# BAT.net
KiCad netlist of a schematic drawn in Altium Designer
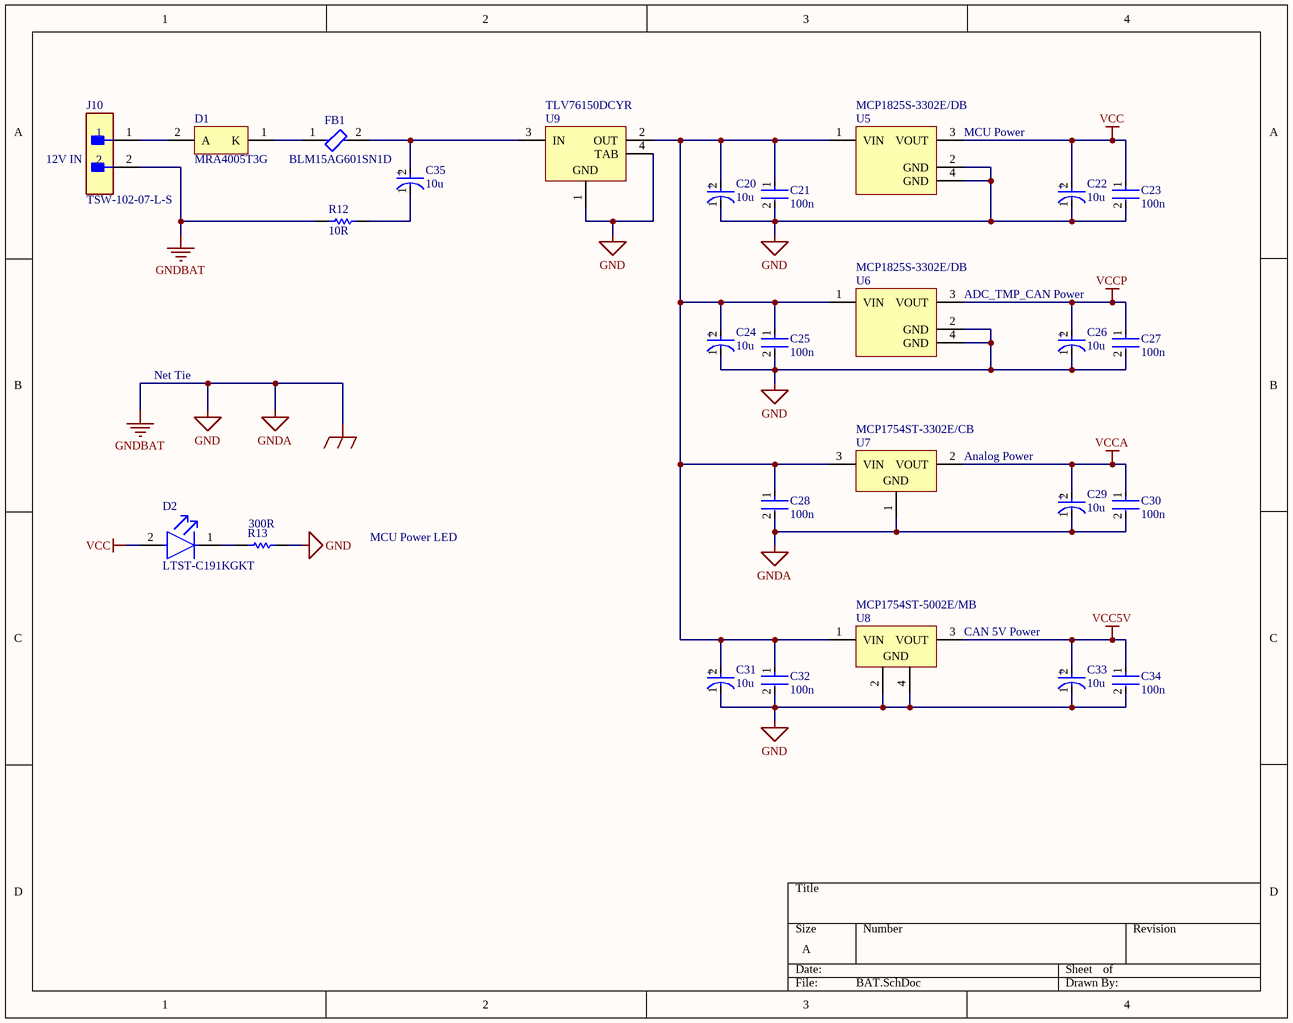
[diagram p0: BAT.SchDoc]

(export (version "E")
  (design (tool "Eeschema 10.0.6"))
  (components
    (comp (ref "C20")
      (value "10u")
      (footprint "FP-TAJA-MFG")
      (description "10uF 6.3V  ±10% 4Ω 1206  SMD Tantalum Capacitor")
      (fields (field (name "VOLTAGE") "6.3V") (field (name "TOLERANCE") "20%"))
      (libsource (lib "Altium Content Vault") (part "203bc49f2ac43e59fd269a8c329ed05"))
    )
    (comp (ref "C21")
      (value "100n")
      (footprint "FP-GRM033-0_03-MFG")
      (description "Chip Multilayer Ceramic Capacitors for General Purpose, 0201, 0.10uF, X5R, 15%, 10%, 6.3V")
      (fields (field (name "VOLTAGE") "6.3V") (field (name "TOLERANCE") "10%"))
      (libsource (lib "Altium Content Vault") (part "b4654b650e69147ec39a6b967a45e02"))
    )
    (comp (ref "C22")
      (value "10u")
      (footprint "FP-TAJA-MFG")
      (description "10uF 6.3V  ±10% 4Ω 1206  SMD Tantalum Capacitor")
      (fields (field (name "VOLTAGE") "6.3V") (field (name "TOLERANCE") "20%"))
      (libsource (lib "Altium Content Vault") (part "203bc49f2ac43e59fd269a8c329ed05"))
    )
    (comp (ref "C23")
      (value "100n")
      (footprint "FP-GRM033-0_03-MFG")
      (description "Chip Multilayer Ceramic Capacitors for General Purpose, 0201, 0.10uF, X5R, 15%, 10%, 6.3V")
      (fields (field (name "VOLTAGE") "6.3V") (field (name "TOLERANCE") "10%"))
      (libsource (lib "Altium Content Vault") (part "b4654b650e69147ec39a6b967a45e02"))
    )
    (comp (ref "C24")
      (value "10u")
      (footprint "FP-TAJA-MFG")
      (description "10uF 6.3V  ±10% 4Ω 1206  SMD Tantalum Capacitor")
      (fields (field (name "VOLTAGE") "6.3V") (field (name "TOLERANCE") "20%"))
      (libsource (lib "Altium Content Vault") (part "203bc49f2ac43e59fd269a8c329ed05"))
    )
    (comp (ref "C25")
      (value "100n")
      (footprint "FP-GRM033-0_03-MFG")
      (description "Chip Multilayer Ceramic Capacitors for General Purpose, 0201, 0.10uF, X5R, 15%, 10%, 6.3V")
      (fields (field (name "VOLTAGE") "6.3V") (field (name "TOLERANCE") "10%"))
      (libsource (lib "Altium Content Vault") (part "b4654b650e69147ec39a6b967a45e02"))
    )
    (comp (ref "C26")
      (value "10u")
      (footprint "FP-TAJA-MFG")
      (description "10uF 6.3V  ±10% 4Ω 1206  SMD Tantalum Capacitor")
      (fields (field (name "VOLTAGE") "6.3V") (field (name "TOLERANCE") "20%"))
      (libsource (lib "Altium Content Vault") (part "203bc49f2ac43e59fd269a8c329ed05"))
    )
    (comp (ref "C27")
      (value "100n")
      (footprint "FP-GRM033-0_03-MFG")
      (description "Chip Multilayer Ceramic Capacitors for General Purpose, 0201, 0.10uF, X5R, 15%, 10%, 6.3V")
      (fields (field (name "VOLTAGE") "6.3V") (field (name "TOLERANCE") "10%"))
      (libsource (lib "Altium Content Vault") (part "b4654b650e69147ec39a6b967a45e02"))
    )
    (comp (ref "C28")
      (value "100n")
      (footprint "FP-GRM033-0_03-MFG")
      (description "Chip Multilayer Ceramic Capacitors for General Purpose, 0201, 0.10uF, X5R, 15%, 10%, 6.3V")
      (fields (field (name "VOLTAGE") "6.3V") (field (name "TOLERANCE") "10%"))
      (libsource (lib "Altium Content Vault") (part "b4654b650e69147ec39a6b967a45e02"))
    )
    (comp (ref "C29")
      (value "10u")
      (footprint "FP-TAJA-MFG")
      (description "10uF 6.3V  ±10% 4Ω 1206  SMD Tantalum Capacitor")
      (fields (field (name "VOLTAGE") "6.3V") (field (name "TOLERANCE") "20%"))
      (libsource (lib "Altium Content Vault") (part "203bc49f2ac43e59fd269a8c329ed05"))
    )
    (comp (ref "C30")
      (value "100n")
      (footprint "FP-GRM033-0_03-MFG")
      (description "Chip Multilayer Ceramic Capacitors for General Purpose, 0201, 0.10uF, X5R, 15%, 10%, 6.3V")
      (fields (field (name "VOLTAGE") "6.3V") (field (name "TOLERANCE") "10%"))
      (libsource (lib "Altium Content Vault") (part "b4654b650e69147ec39a6b967a45e02"))
    )
    (comp (ref "C31")
      (value "10u")
      (footprint "FP-TAJA-MFG")
      (description "10uF 6.3V  ±10% 4Ω 1206  SMD Tantalum Capacitor")
      (fields (field (name "VOLTAGE") "6.3V") (field (name "TOLERANCE") "20%"))
      (libsource (lib "Altium Content Vault") (part "203bc49f2ac43e59fd269a8c329ed05"))
    )
    (comp (ref "C32")
      (value "100n")
      (footprint "FP-GRM033-0_03-MFG")
      (description "Chip Multilayer Ceramic Capacitors for General Purpose, 0201, 0.10uF, X5R, 15%, 10%, 6.3V")
      (fields (field (name "VOLTAGE") "6.3V") (field (name "TOLERANCE") "10%"))
      (libsource (lib "Altium Content Vault") (part "b4654b650e69147ec39a6b967a45e02"))
    )
    (comp (ref "C33")
      (value "10u")
      (footprint "FP-TAJA-MFG")
      (description "10uF 6.3V  ±10% 4Ω 1206  SMD Tantalum Capacitor")
      (fields (field (name "VOLTAGE") "6.3V") (field (name "TOLERANCE") "20%"))
      (libsource (lib "Altium Content Vault") (part "203bc49f2ac43e59fd269a8c329ed05"))
    )
    (comp (ref "C34")
      (value "100n")
      (footprint "FP-GRM033-0_03-MFG")
      (description "Chip Multilayer Ceramic Capacitors for General Purpose, 0201, 0.10uF, X5R, 15%, 10%, 6.3V")
      (fields (field (name "VOLTAGE") "6.3V") (field (name "TOLERANCE") "10%"))
      (libsource (lib "Altium Content Vault") (part "b4654b650e69147ec39a6b967a45e02"))
    )
    (comp (ref "C35")
      (value "10u")
      (footprint "FP-TAJA-MFG")
      (description "10uF 6.3V  ±10% 4Ω 1206  SMD Tantalum Capacitor")
      (fields (field (name "VOLTAGE") "6.3V") (field (name "TOLERANCE") "20%"))
      (libsource (lib "Altium Content Vault") (part "203bc49f2ac43e59fd269a8c329ed05"))
    )
    (comp (ref "D1")
      (value "MRA4005T3G")
      (footprint "ONSC-SMA-2-403D-02_V")
      (description "Surface Mount Standard Recovery Power Rectifier, 2-Pin SMA, Pb-Free, Tape and Reel")
      (fields (field (name "MANUFACTURER") "On Semiconductor"))
      (libsource (lib "Altium Content Vault") (part "ONSC-D-K1A2-2_A"))
    )
    (comp (ref "D2")
      (value "LTST-C191KGKT")
      (footprint "FP-LTST-C191KSKT-MFG")
      (description "LED YELLOW CLEAR SMD")
      (libsource (lib "Altium Content Vault") (part "8706943c75ba83719d021d2fdc84c58"))
    )
    (comp (ref "FB1")
      (value "BLM15AG601SN1D")
      (footprint "FP-BLM15-0_05-MFG")
      (description "Chip Ferrite Bead, 0402, 600Ω @ 100MHz, 0.52Ω, 25%, 300mA")
      (fields (field (name "TOLERANCE") "25%"))
      (libsource (lib "Altium Content Vault") (part "5f30dd21d616792df468990f7003faa"))
    )
    (comp (ref "J10")
      (value "TSW-102-07-L-S")
      (footprint "FP-TSW-102-07-L-S-MFG")
      (description "CONN HEADER VERT 2POS 2.54MM")
      (libsource (lib "Altium Content Vault") (part "3bc925449376181038e59eaffc5286c"))
    )
    (comp (ref "R12")
      (value "10R")
      (footprint "RESC2013X60X35ML10T20")
      (description "Chip Resistor, 10 Ohm, +/- 1%, 0.125 W, -55 to 155 degC, 0805 (2012 Metric), RoHS, Tape and Reel")
      (fields (field (name "MANUFACTURER") "Yageo") (field (name "TOLERANCE") "1%"))
      (libsource (lib "Altium Content Vault") (part "RES-2"))
    )
    (comp (ref "R13")
      (value "300R")
      (footprint "RESC1608X55X30LL20T20")
      (fields (field (name "PART NUMBER") "ERA3AEB301V") (field (name "MANUFACTURER") "Panasonic"))
      (libsource (lib "Altium Content Vault") (part "RES"))
    )
    (comp (ref "U5")
      (value "MCP1825S-3302E/DB")
      (footprint "SOT-223-DB3_N")
      (description "500 mA, Low Voltage, Low Quiescent Current LDO Regulator, 3-Pin SOT-223, Extended Temperature")
      (libsource (lib "Altium Content Vault") (part "PM-LINEREG-MCP1825-IL4"))
    )
    (comp (ref "U6")
      (value "MCP1825S-3302E/DB")
      (footprint "SOT-223-DB3_N")
      (description "500 mA, Low Voltage, Low Quiescent Current LDO Regulator, 3-Pin SOT-223, Extended Temperature")
      (libsource (lib "Altium Content Vault") (part "PM-LINEREG-MCP1825-IL4"))
    )
    (comp (ref "U7")
      (value "MCP1754ST-3302E/CB")
      (footprint "MCHP-SOT-23A-CB3_N")
      (description "150 mA, 16 V, High Performance LDO, -40 to 125 degC, 3-pin SOT-23A (CB3), Tape and Reel")
      (fields (field (name "MANUFACTURER") "Microchip"))
      (libsource (lib "Altium Content Vault") (part "MCHP-MCP17XX-SOT-23X-3"))
    )
    (comp (ref "U8")
      (value "MCP1754ST-5002E/MB")
      (footprint "MCHP-SOT-89-MB3_L")
      (description "150 mA, 16 V, High Performance LDO, -40 to 125 degC, 3-pin SOT-89 (MB3), Tape and Reel")
      (fields (field (name "MANUFACTURER") "Microchip"))
      (libsource (lib "Altium Content Vault") (part "MCHP-MCP1754S-SOT-xxx"))
    )
    (comp (ref "U9")
      (value "TLV76150DCYR")
      (footprint "DCY0004A_L")
      (description "800mA Low-Dropout Linear Regulator, 4-pin SOT-223")
      (fields (field (name "PARTNUMBER") "LM1117MPX-5.0") (field (name "MANUFACTURER") "Texas Instruments"))
      (libsource (lib "Altium Content Vault") (part "PM-REG-LM1086-SOT4"))
    )
  )
  (nets
    (net (code "1") (name "GND") (class "Default")
      (node (ref "C20") (pin "1") (pinfunction "C_1") (pintype "passive"))
      (node (ref "C21") (pin "2") (pinfunction "2_2") (pintype "passive"))
      (node (ref "C22") (pin "1") (pinfunction "C_1") (pintype "passive"))
      (node (ref "C23") (pin "2") (pinfunction "2_2") (pintype "passive"))
      (node (ref "C24") (pin "1") (pinfunction "C_1") (pintype "passive"))
      (node (ref "C25") (pin "2") (pinfunction "2_2") (pintype "passive"))
      (node (ref "C26") (pin "1") (pinfunction "C_1") (pintype "passive"))
      (node (ref "C27") (pin "2") (pinfunction "2_2") (pintype "passive"))
      (node (ref "C28") (pin "2") (pinfunction "2_2") (pintype "passive"))
      (node (ref "C29") (pin "1") (pinfunction "C_1") (pintype "passive"))
      (node (ref "C30") (pin "2") (pinfunction "2_2") (pintype "passive"))
      (node (ref "C31") (pin "1") (pinfunction "C_1") (pintype "passive"))
      (node (ref "C32") (pin "2") (pinfunction "2_2") (pintype "passive"))
      (node (ref "C33") (pin "1") (pinfunction "C_1") (pintype "passive"))
      (node (ref "C34") (pin "2") (pinfunction "2_2") (pintype "passive"))
      (node (ref "J10") (pin "2") (pinfunction "2_2") (pintype "passive"))
      (node (ref "R12") (pin "1") (pinfunction "1_1") (pintype "passive"))
      (node (ref "R13") (pin "2") (pinfunction "2_2") (pintype "passive"))
      (node (ref "U5") (pin "2") (pinfunction "GND_2") (pintype "power_in"))
      (node (ref "U5") (pin "4") (pinfunction "GND_4") (pintype "power_in"))
      (node (ref "U6") (pin "2") (pinfunction "GND_2") (pintype "power_in"))
      (node (ref "U6") (pin "4") (pinfunction "GND_4") (pintype "power_in"))
      (node (ref "U7") (pin "1") (pinfunction "GND_1") (pintype "power_in"))
      (node (ref "U8") (pin "2") (pinfunction "GND_2") (pintype "power_in"))
      (node (ref "U8") (pin "4") (pinfunction "GND_4") (pintype "power_in"))
      (node (ref "U9") (pin "1") (pinfunction "GND_1") (pintype "power_in"))
      (node (ref "U9") (pin "4") (pinfunction "TAB_4") (pintype "power_in"))
    )
    (net (code "2") (name "Net-(C20-A)") (class "Default")
      (node (ref "C20") (pin "2") (pinfunction "A_2") (pintype "passive"))
      (node (ref "C21") (pin "1") (pinfunction "1_1") (pintype "passive"))
      (node (ref "C24") (pin "2") (pinfunction "A_2") (pintype "passive"))
      (node (ref "C25") (pin "1") (pinfunction "1_1") (pintype "passive"))
      (node (ref "C28") (pin "1") (pinfunction "1_1") (pintype "passive"))
      (node (ref "C31") (pin "2") (pinfunction "A_2") (pintype "passive"))
      (node (ref "C32") (pin "1") (pinfunction "1_1") (pintype "passive"))
      (node (ref "U5") (pin "1") (pinfunction "VIN_1") (pintype "power_in"))
      (node (ref "U6") (pin "1") (pinfunction "VIN_1") (pintype "power_in"))
      (node (ref "U7") (pin "3") (pinfunction "VIN_3") (pintype "power_in"))
      (node (ref "U8") (pin "1") (pinfunction "VIN_1") (pintype "power_in"))
      (node (ref "U9") (pin "2") (pinfunction "OUT_2") (pintype "power_in"))
    )
    (net (code "3") (name "Net-(C35-A)") (class "Default")
      (node (ref "C35") (pin "2") (pinfunction "A_2") (pintype "passive"))
      (node (ref "FB1") (pin "2") (pinfunction "2_2") (pintype "passive"))
      (node (ref "U9") (pin "3") (pinfunction "IN_3") (pintype "power_in"))
    )
    (net (code "4") (name "Net-(C35-C)") (class "Default")
      (node (ref "C35") (pin "1") (pinfunction "C_1") (pintype "passive"))
      (node (ref "R12") (pin "2") (pinfunction "2_2") (pintype "passive"))
    )
    (net (code "5") (name "Net-(D1-A)") (class "Default")
      (node (ref "D1") (pin "2") (pinfunction "A_2") (pintype "passive"))
      (node (ref "J10") (pin "1") (pinfunction "1_1") (pintype "passive"))
    )
    (net (code "6") (name "Net-(D1-K)") (class "Default")
      (node (ref "D1") (pin "1") (pinfunction "K_1") (pintype "passive"))
      (node (ref "FB1") (pin "1") (pinfunction "1_1") (pintype "passive"))
    )
    (net (code "7") (name "Net-(D2-C)") (class "Default")
      (node (ref "D2") (pin "1") (pinfunction "C_1") (pintype "passive"))
      (node (ref "R13") (pin "1") (pinfunction "1_1") (pintype "passive"))
    )
    (net (code "8") (name "VCC") (class "Default")
      (node (ref "C22") (pin "2") (pinfunction "A_2") (pintype "passive"))
      (node (ref "C23") (pin "1") (pinfunction "1_1") (pintype "passive"))
      (node (ref "D2") (pin "2") (pinfunction "A_2") (pintype "passive"))
      (node (ref "U5") (pin "3") (pinfunction "VOUT_3") (pintype "power_in"))
    )
    (net (code "9") (name "VCC5V") (class "Default")
      (node (ref "C33") (pin "2") (pinfunction "A_2") (pintype "passive"))
      (node (ref "C34") (pin "1") (pinfunction "1_1") (pintype "passive"))
      (node (ref "U8") (pin "3") (pinfunction "VOUT_3") (pintype "power_in"))
    )
    (net (code "10") (name "VCCA") (class "Default")
      (node (ref "C29") (pin "2") (pinfunction "A_2") (pintype "passive"))
      (node (ref "C30") (pin "1") (pinfunction "1_1") (pintype "passive"))
      (node (ref "U7") (pin "2") (pinfunction "VOUT_2") (pintype "power_in"))
    )
    (net (code "11") (name "VCCP") (class "Default")
      (node (ref "C26") (pin "2") (pinfunction "A_2") (pintype "passive"))
      (node (ref "C27") (pin "1") (pinfunction "1_1") (pintype "passive"))
      (node (ref "U6") (pin "3") (pinfunction "VOUT_3") (pintype "power_in"))
    )
  )
)
